# Sheet_2.net
KiCad netlist of a schematic drawn in Altium Designer
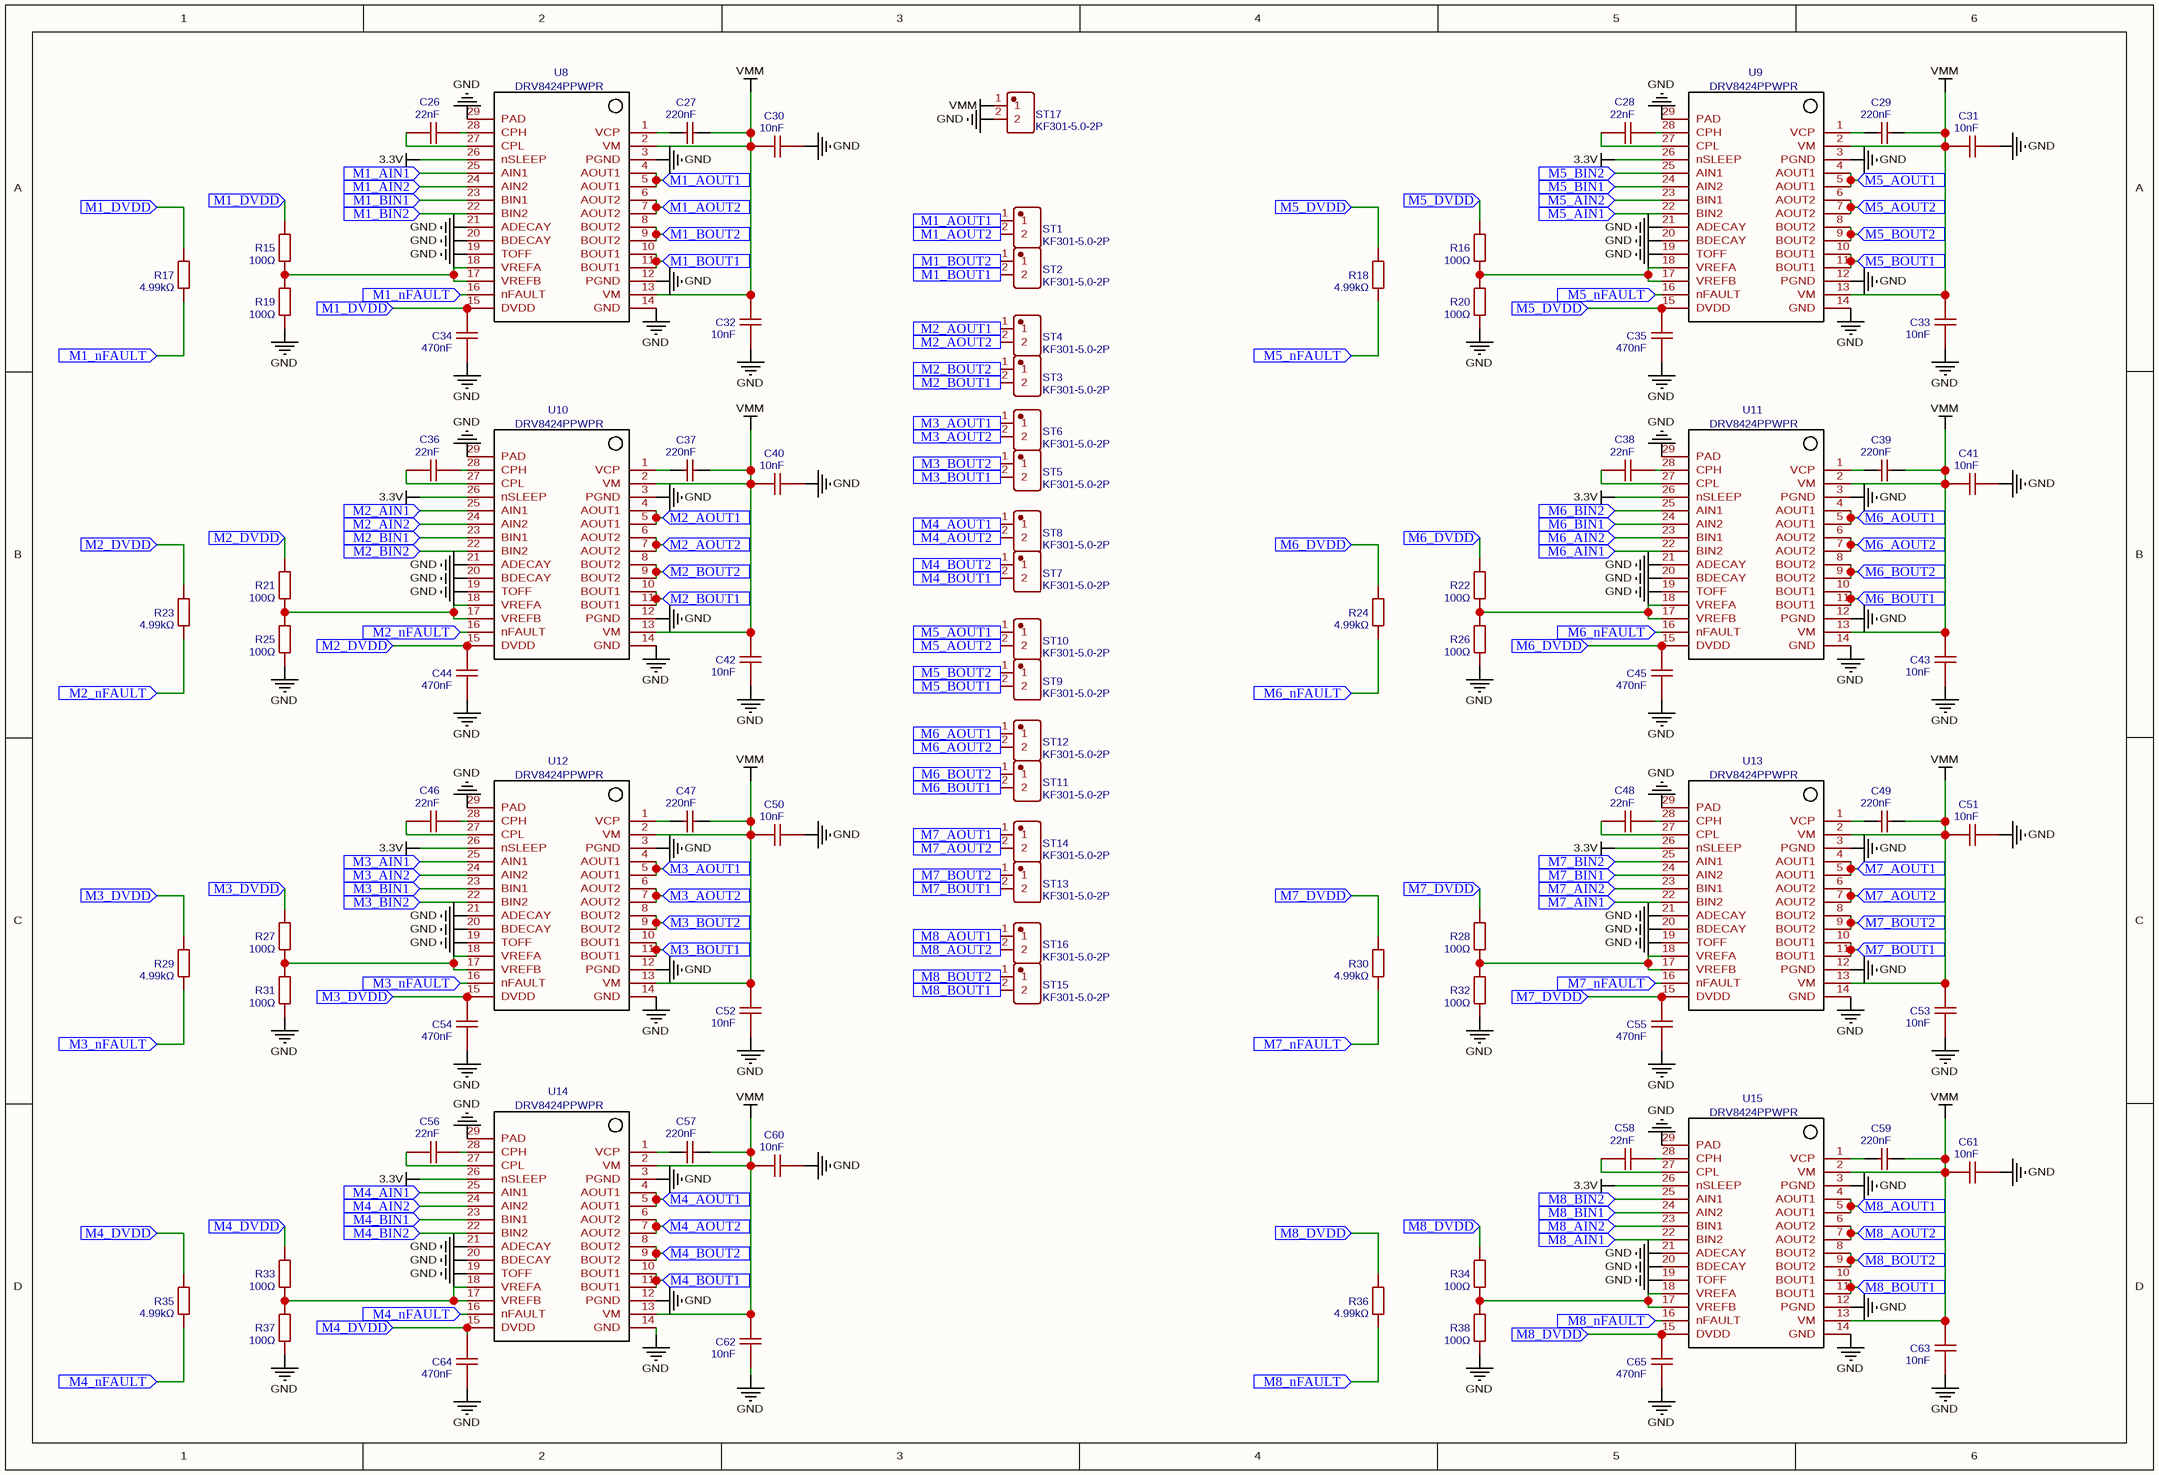
[diagram p0: Sheet_2.schdoc]

(export (version "E")
  (design (tool "Eeschema 10.0.6"))
  (components
    (comp (ref "C26")
      (value "22nF")
      (fields
        (field (name "BOM_SUPPLIER PART") "C561834")
        (field (name "BOM_MANUFACTURER PART") "C0805C223K1RACAUTO")
        (field (name "CONTRIBUTOR") "LCSC")
      )
      (libsource (lib "altium-import") (part "root_0_22nF_"))
    )
    (comp (ref "C27")
      (value "220nF")
      (fields
        (field (name "BOM_MANUFACTURER PART") "CC0805KRX7R8BB224")
        (field (name "BOM_SUPPLIER PART") "C107139")
      )
      (libsource (lib "altium-import") (part "root_0_220nF_"))
    )
    (comp (ref "C28")
      (value "22nF")
      (fields
        (field (name "BOM_SUPPLIER PART") "C561834")
        (field (name "BOM_MANUFACTURER PART") "C0805C223K1RACAUTO")
        (field (name "CONTRIBUTOR") "LCSC")
      )
      (libsource (lib "altium-import") (part "root_0_22nF_"))
    )
    (comp (ref "C29")
      (value "220nF")
      (fields
        (field (name "BOM_MANUFACTURER PART") "CC0805KRX7R8BB224")
        (field (name "BOM_SUPPLIER PART") "C107139")
      )
      (libsource (lib "altium-import") (part "root_0_220nF_"))
    )
    (comp (ref "C30")
      (value "10nF")
      (fields
        (field (name "BOM_MANUFACTURER PART") "CC0805KRX7R9BB103")
        (field (name "BOM_SUPPLIER PART") "C83170")
      )
      (libsource (lib "altium-import") (part "root_2_10nF_"))
    )
    (comp (ref "C31")
      (value "10nF")
      (fields
        (field (name "BOM_MANUFACTURER PART") "CC0805KRX7R9BB103")
        (field (name "BOM_SUPPLIER PART") "C83170")
      )
      (libsource (lib "altium-import") (part "root_2_10nF_"))
    )
    (comp (ref "C32")
      (value "10nF")
      (fields
        (field (name "BOM_MANUFACTURER PART") "CC0805KRX7R9BB103")
        (field (name "BOM_SUPPLIER PART") "C83170")
      )
      (libsource (lib "altium-import") (part "root_3_10nF_"))
    )
    (comp (ref "C33")
      (value "10nF")
      (fields
        (field (name "BOM_MANUFACTURER PART") "CC0805KRX7R9BB103")
        (field (name "BOM_SUPPLIER PART") "C83170")
      )
      (libsource (lib "altium-import") (part "root_3_10nF_"))
    )
    (comp (ref "C34")
      (value "470nF")
      (fields
        (field (name "BOM_SUPPLIER PART") "C520079")
        (field (name "BOM_MANUFACTURER PART") "CC0805JKX7R7BB474")
        (field (name "CONTRIBUTOR") "LCSC")
      )
      (libsource (lib "altium-import") (part "root_3_470nF_"))
    )
    (comp (ref "C35")
      (value "470nF")
      (fields
        (field (name "BOM_SUPPLIER PART") "C520079")
        (field (name "BOM_MANUFACTURER PART") "CC0805JKX7R7BB474")
        (field (name "CONTRIBUTOR") "LCSC")
      )
      (libsource (lib "altium-import") (part "root_3_470nF_"))
    )
    (comp (ref "C36")
      (value "22nF")
      (fields
        (field (name "BOM_SUPPLIER PART") "C561834")
        (field (name "BOM_MANUFACTURER PART") "C0805C223K1RACAUTO")
        (field (name "CONTRIBUTOR") "LCSC")
      )
      (libsource (lib "altium-import") (part "root_0_22nF_"))
    )
    (comp (ref "C37")
      (value "220nF")
      (fields
        (field (name "BOM_MANUFACTURER PART") "CC0805KRX7R8BB224")
        (field (name "BOM_SUPPLIER PART") "C107139")
      )
      (libsource (lib "altium-import") (part "root_0_220nF_"))
    )
    (comp (ref "C38")
      (value "22nF")
      (fields
        (field (name "BOM_SUPPLIER PART") "C561834")
        (field (name "BOM_MANUFACTURER PART") "C0805C223K1RACAUTO")
        (field (name "CONTRIBUTOR") "LCSC")
      )
      (libsource (lib "altium-import") (part "root_0_22nF_"))
    )
    (comp (ref "C39")
      (value "220nF")
      (fields
        (field (name "BOM_MANUFACTURER PART") "CC0805KRX7R8BB224")
        (field (name "BOM_SUPPLIER PART") "C107139")
      )
      (libsource (lib "altium-import") (part "root_0_220nF_"))
    )
    (comp (ref "C40")
      (value "10nF")
      (fields
        (field (name "BOM_MANUFACTURER PART") "CC0805KRX7R9BB103")
        (field (name "BOM_SUPPLIER PART") "C83170")
      )
      (libsource (lib "altium-import") (part "root_2_10nF_"))
    )
    (comp (ref "C41")
      (value "10nF")
      (fields
        (field (name "BOM_MANUFACTURER PART") "CC0805KRX7R9BB103")
        (field (name "BOM_SUPPLIER PART") "C83170")
      )
      (libsource (lib "altium-import") (part "root_2_10nF_"))
    )
    (comp (ref "C42")
      (value "10nF")
      (fields
        (field (name "BOM_MANUFACTURER PART") "CC0805KRX7R9BB103")
        (field (name "BOM_SUPPLIER PART") "C83170")
      )
      (libsource (lib "altium-import") (part "root_3_10nF_"))
    )
    (comp (ref "C43")
      (value "10nF")
      (fields
        (field (name "BOM_MANUFACTURER PART") "CC0805KRX7R9BB103")
        (field (name "BOM_SUPPLIER PART") "C83170")
      )
      (libsource (lib "altium-import") (part "root_3_10nF_"))
    )
    (comp (ref "C44")
      (value "470nF")
      (fields
        (field (name "BOM_SUPPLIER PART") "C520079")
        (field (name "BOM_MANUFACTURER PART") "CC0805JKX7R7BB474")
        (field (name "CONTRIBUTOR") "LCSC")
      )
      (libsource (lib "altium-import") (part "root_3_470nF_"))
    )
    (comp (ref "C45")
      (value "470nF")
      (fields
        (field (name "BOM_SUPPLIER PART") "C520079")
        (field (name "BOM_MANUFACTURER PART") "CC0805JKX7R7BB474")
        (field (name "CONTRIBUTOR") "LCSC")
      )
      (libsource (lib "altium-import") (part "root_3_470nF_"))
    )
    (comp (ref "C46")
      (value "22nF")
      (fields
        (field (name "BOM_SUPPLIER PART") "C561834")
        (field (name "BOM_MANUFACTURER PART") "C0805C223K1RACAUTO")
        (field (name "CONTRIBUTOR") "LCSC")
      )
      (libsource (lib "altium-import") (part "root_0_22nF_"))
    )
    (comp (ref "C47")
      (value "220nF")
      (fields
        (field (name "BOM_MANUFACTURER PART") "CC0805KRX7R8BB224")
        (field (name "BOM_SUPPLIER PART") "C107139")
      )
      (libsource (lib "altium-import") (part "root_0_220nF_"))
    )
    (comp (ref "C48")
      (value "22nF")
      (fields
        (field (name "BOM_SUPPLIER PART") "C561834")
        (field (name "BOM_MANUFACTURER PART") "C0805C223K1RACAUTO")
        (field (name "CONTRIBUTOR") "LCSC")
      )
      (libsource (lib "altium-import") (part "root_0_22nF_"))
    )
    (comp (ref "C49")
      (value "220nF")
      (fields
        (field (name "BOM_MANUFACTURER PART") "CC0805KRX7R8BB224")
        (field (name "BOM_SUPPLIER PART") "C107139")
      )
      (libsource (lib "altium-import") (part "root_0_220nF_"))
    )
    (comp (ref "C50")
      (value "10nF")
      (fields
        (field (name "BOM_MANUFACTURER PART") "CC0805KRX7R9BB103")
        (field (name "BOM_SUPPLIER PART") "C83170")
      )
      (libsource (lib "altium-import") (part "root_2_10nF_"))
    )
    (comp (ref "C51")
      (value "10nF")
      (fields
        (field (name "BOM_MANUFACTURER PART") "CC0805KRX7R9BB103")
        (field (name "BOM_SUPPLIER PART") "C83170")
      )
      (libsource (lib "altium-import") (part "root_2_10nF_"))
    )
    (comp (ref "C52")
      (value "10nF")
      (fields
        (field (name "BOM_MANUFACTURER PART") "CC0805KRX7R9BB103")
        (field (name "BOM_SUPPLIER PART") "C83170")
      )
      (libsource (lib "altium-import") (part "root_3_10nF_"))
    )
    (comp (ref "C53")
      (value "10nF")
      (fields
        (field (name "BOM_MANUFACTURER PART") "CC0805KRX7R9BB103")
        (field (name "BOM_SUPPLIER PART") "C83170")
      )
      (libsource (lib "altium-import") (part "root_3_10nF_"))
    )
    (comp (ref "C54")
      (value "470nF")
      (fields
        (field (name "BOM_SUPPLIER PART") "C520079")
        (field (name "BOM_MANUFACTURER PART") "CC0805JKX7R7BB474")
        (field (name "CONTRIBUTOR") "LCSC")
      )
      (libsource (lib "altium-import") (part "root_3_470nF_"))
    )
    (comp (ref "C55")
      (value "470nF")
      (fields
        (field (name "BOM_SUPPLIER PART") "C520079")
        (field (name "BOM_MANUFACTURER PART") "CC0805JKX7R7BB474")
        (field (name "CONTRIBUTOR") "LCSC")
      )
      (libsource (lib "altium-import") (part "root_3_470nF_"))
    )
    (comp (ref "C56")
      (value "22nF")
      (fields
        (field (name "BOM_SUPPLIER PART") "C561834")
        (field (name "BOM_MANUFACTURER PART") "C0805C223K1RACAUTO")
        (field (name "CONTRIBUTOR") "LCSC")
      )
      (libsource (lib "altium-import") (part "root_0_22nF_"))
    )
    (comp (ref "C57")
      (value "220nF")
      (fields
        (field (name "BOM_MANUFACTURER PART") "CC0805KRX7R8BB224")
        (field (name "BOM_SUPPLIER PART") "C107139")
      )
      (libsource (lib "altium-import") (part "root_0_220nF_"))
    )
    (comp (ref "C58")
      (value "22nF")
      (fields
        (field (name "BOM_SUPPLIER PART") "C561834")
        (field (name "BOM_MANUFACTURER PART") "C0805C223K1RACAUTO")
        (field (name "CONTRIBUTOR") "LCSC")
      )
      (libsource (lib "altium-import") (part "root_0_22nF_"))
    )
    (comp (ref "C59")
      (value "220nF")
      (fields
        (field (name "BOM_MANUFACTURER PART") "CC0805KRX7R8BB224")
        (field (name "BOM_SUPPLIER PART") "C107139")
      )
      (libsource (lib "altium-import") (part "root_0_220nF_"))
    )
    (comp (ref "C60")
      (value "10nF")
      (fields
        (field (name "BOM_MANUFACTURER PART") "CC0805KRX7R9BB103")
        (field (name "BOM_SUPPLIER PART") "C83170")
      )
      (libsource (lib "altium-import") (part "root_2_10nF_"))
    )
    (comp (ref "C61")
      (value "10nF")
      (fields
        (field (name "BOM_MANUFACTURER PART") "CC0805KRX7R9BB103")
        (field (name "BOM_SUPPLIER PART") "C83170")
      )
      (libsource (lib "altium-import") (part "root_2_10nF_"))
    )
    (comp (ref "C62")
      (value "10nF")
      (fields
        (field (name "BOM_MANUFACTURER PART") "CC0805KRX7R9BB103")
        (field (name "BOM_SUPPLIER PART") "C83170")
      )
      (libsource (lib "altium-import") (part "root_3_10nF_"))
    )
    (comp (ref "C63")
      (value "10nF")
      (fields
        (field (name "BOM_MANUFACTURER PART") "CC0805KRX7R9BB103")
        (field (name "BOM_SUPPLIER PART") "C83170")
      )
      (libsource (lib "altium-import") (part "root_3_10nF_"))
    )
    (comp (ref "C64")
      (value "470nF")
      (fields
        (field (name "BOM_SUPPLIER PART") "C520079")
        (field (name "BOM_MANUFACTURER PART") "CC0805JKX7R7BB474")
        (field (name "CONTRIBUTOR") "LCSC")
      )
      (libsource (lib "altium-import") (part "root_3_470nF_"))
    )
    (comp (ref "C65")
      (value "470nF")
      (fields
        (field (name "BOM_SUPPLIER PART") "C520079")
        (field (name "BOM_MANUFACTURER PART") "CC0805JKX7R7BB474")
        (field (name "CONTRIBUTOR") "LCSC")
      )
      (libsource (lib "altium-import") (part "root_3_470nF_"))
    )
    (comp (ref "R15")
      (value "100Ω")
      (fields
        (field (name "BOM_SUPPLIER PART") "C176206")
        (field (name "BOM_MANUFACTURER PART") "QR0805J100RP05")
        (field (name "CONTRIBUTOR") "LCSC")
      )
      (libsource (lib "altium-import") (part "root_1_100Ω_"))
    )
    (comp (ref "R16")
      (value "100Ω")
      (fields
        (field (name "BOM_SUPPLIER PART") "C176206")
        (field (name "BOM_MANUFACTURER PART") "QR0805J100RP05")
        (field (name "CONTRIBUTOR") "LCSC")
      )
      (libsource (lib "altium-import") (part "root_1_100Ω_"))
    )
    (comp (ref "R17")
      (value "4.99kΩ")
      (fields
        (field (name "BOM_SUPPLIER PART") "C325814")
        (field (name "BOM_MANUFACTURER PART") "RMC08054.99K1%N")
        (field (name "CONTRIBUTOR") "LCSC")
      )
      (libsource (lib "altium-import") (part "root_1_4.99kΩ_"))
    )
    (comp (ref "R18")
      (value "4.99kΩ")
      (fields
        (field (name "BOM_SUPPLIER PART") "C325814")
        (field (name "BOM_MANUFACTURER PART") "RMC08054.99K1%N")
        (field (name "CONTRIBUTOR") "LCSC")
      )
      (libsource (lib "altium-import") (part "root_1_4.99kΩ_"))
    )
    (comp (ref "R19")
      (value "100Ω")
      (fields
        (field (name "BOM_SUPPLIER PART") "C176206")
        (field (name "BOM_MANUFACTURER PART") "QR0805J100RP05")
        (field (name "CONTRIBUTOR") "LCSC")
      )
      (libsource (lib "altium-import") (part "root_1_100Ω_"))
    )
    (comp (ref "R20")
      (value "100Ω")
      (fields
        (field (name "BOM_SUPPLIER PART") "C176206")
        (field (name "BOM_MANUFACTURER PART") "QR0805J100RP05")
        (field (name "CONTRIBUTOR") "LCSC")
      )
      (libsource (lib "altium-import") (part "root_1_100Ω_"))
    )
    (comp (ref "R21")
      (value "100Ω")
      (fields
        (field (name "BOM_SUPPLIER PART") "C176206")
        (field (name "BOM_MANUFACTURER PART") "QR0805J100RP05")
        (field (name "CONTRIBUTOR") "LCSC")
      )
      (libsource (lib "altium-import") (part "root_1_100Ω_"))
    )
    (comp (ref "R22")
      (value "100Ω")
      (fields
        (field (name "BOM_SUPPLIER PART") "C176206")
        (field (name "BOM_MANUFACTURER PART") "QR0805J100RP05")
        (field (name "CONTRIBUTOR") "LCSC")
      )
      (libsource (lib "altium-import") (part "root_1_100Ω_"))
    )
    (comp (ref "R23")
      (value "4.99kΩ")
      (fields
        (field (name "BOM_SUPPLIER PART") "C325814")
        (field (name "BOM_MANUFACTURER PART") "RMC08054.99K1%N")
        (field (name "CONTRIBUTOR") "LCSC")
      )
      (libsource (lib "altium-import") (part "root_1_4.99kΩ_"))
    )
    (comp (ref "R24")
      (value "4.99kΩ")
      (fields
        (field (name "BOM_SUPPLIER PART") "C325814")
        (field (name "BOM_MANUFACTURER PART") "RMC08054.99K1%N")
        (field (name "CONTRIBUTOR") "LCSC")
      )
      (libsource (lib "altium-import") (part "root_1_4.99kΩ_"))
    )
    (comp (ref "R25")
      (value "100Ω")
      (fields
        (field (name "BOM_SUPPLIER PART") "C176206")
        (field (name "BOM_MANUFACTURER PART") "QR0805J100RP05")
        (field (name "CONTRIBUTOR") "LCSC")
      )
      (libsource (lib "altium-import") (part "root_1_100Ω_"))
    )
    (comp (ref "R26")
      (value "100Ω")
      (fields
        (field (name "BOM_SUPPLIER PART") "C176206")
        (field (name "BOM_MANUFACTURER PART") "QR0805J100RP05")
        (field (name "CONTRIBUTOR") "LCSC")
      )
      (libsource (lib "altium-import") (part "root_1_100Ω_"))
    )
    (comp (ref "R27")
      (value "100Ω")
      (fields
        (field (name "BOM_SUPPLIER PART") "C176206")
        (field (name "BOM_MANUFACTURER PART") "QR0805J100RP05")
        (field (name "CONTRIBUTOR") "LCSC")
      )
      (libsource (lib "altium-import") (part "root_1_100Ω_"))
    )
    (comp (ref "R28")
      (value "100Ω")
      (fields
        (field (name "BOM_SUPPLIER PART") "C176206")
        (field (name "BOM_MANUFACTURER PART") "QR0805J100RP05")
        (field (name "CONTRIBUTOR") "LCSC")
      )
      (libsource (lib "altium-import") (part "root_1_100Ω_"))
    )
    (comp (ref "R29")
      (value "4.99kΩ")
      (fields
        (field (name "BOM_SUPPLIER PART") "C325814")
        (field (name "BOM_MANUFACTURER PART") "RMC08054.99K1%N")
        (field (name "CONTRIBUTOR") "LCSC")
      )
      (libsource (lib "altium-import") (part "root_1_4.99kΩ_"))
    )
    (comp (ref "R30")
      (value "4.99kΩ")
      (fields
        (field (name "BOM_SUPPLIER PART") "C325814")
        (field (name "BOM_MANUFACTURER PART") "RMC08054.99K1%N")
        (field (name "CONTRIBUTOR") "LCSC")
      )
      (libsource (lib "altium-import") (part "root_1_4.99kΩ_"))
    )
    (comp (ref "R31")
      (value "100Ω")
      (fields
        (field (name "BOM_SUPPLIER PART") "C176206")
        (field (name "BOM_MANUFACTURER PART") "QR0805J100RP05")
        (field (name "CONTRIBUTOR") "LCSC")
      )
      (libsource (lib "altium-import") (part "root_1_100Ω_"))
    )
    (comp (ref "R32")
      (value "100Ω")
      (fields
        (field (name "BOM_SUPPLIER PART") "C176206")
        (field (name "BOM_MANUFACTURER PART") "QR0805J100RP05")
        (field (name "CONTRIBUTOR") "LCSC")
      )
      (libsource (lib "altium-import") (part "root_1_100Ω_"))
    )
    (comp (ref "R33")
      (value "100Ω")
      (fields
        (field (name "BOM_SUPPLIER PART") "C176206")
        (field (name "BOM_MANUFACTURER PART") "QR0805J100RP05")
        (field (name "CONTRIBUTOR") "LCSC")
      )
      (libsource (lib "altium-import") (part "root_1_100Ω_"))
    )
    (comp (ref "R34")
      (value "100Ω")
      (fields
        (field (name "BOM_SUPPLIER PART") "C176206")
        (field (name "BOM_MANUFACTURER PART") "QR0805J100RP05")
        (field (name "CONTRIBUTOR") "LCSC")
      )
      (libsource (lib "altium-import") (part "root_1_100Ω_"))
    )
    (comp (ref "R35")
      (value "4.99kΩ")
      (fields
        (field (name "BOM_SUPPLIER PART") "C325814")
        (field (name "BOM_MANUFACTURER PART") "RMC08054.99K1%N")
        (field (name "CONTRIBUTOR") "LCSC")
      )
      (libsource (lib "altium-import") (part "root_1_4.99kΩ_"))
    )
    (comp (ref "R36")
      (value "4.99kΩ")
      (fields
        (field (name "BOM_SUPPLIER PART") "C325814")
        (field (name "BOM_MANUFACTURER PART") "RMC08054.99K1%N")
        (field (name "CONTRIBUTOR") "LCSC")
      )
      (libsource (lib "altium-import") (part "root_1_4.99kΩ_"))
    )
    (comp (ref "R37")
      (value "100Ω")
      (fields
        (field (name "BOM_SUPPLIER PART") "C176206")
        (field (name "BOM_MANUFACTURER PART") "QR0805J100RP05")
        (field (name "CONTRIBUTOR") "LCSC")
      )
      (libsource (lib "altium-import") (part "root_1_100Ω_"))
    )
    (comp (ref "R38")
      (value "100Ω")
      (fields
        (field (name "BOM_SUPPLIER PART") "C176206")
        (field (name "BOM_MANUFACTURER PART") "QR0805J100RP05")
        (field (name "CONTRIBUTOR") "LCSC")
      )
      (libsource (lib "altium-import") (part "root_1_100Ω_"))
    )
    (comp (ref "ST1")
      (value "KF301-5.0-2P")
      (fields (field (name "BOM_SUPPLIER PART") "C474881") (field (name "CONTRIBUTOR") "LCSC"))
      (libsource (lib "altium-import") (part "root_0_KF301-5.0-2P_"))
    )
    (comp (ref "ST2")
      (value "KF301-5.0-2P")
      (fields (field (name "BOM_SUPPLIER PART") "C474881") (field (name "CONTRIBUTOR") "LCSC"))
      (libsource (lib "altium-import") (part "root_0_KF301-5.0-2P_"))
    )
    (comp (ref "ST3")
      (value "KF301-5.0-2P")
      (fields (field (name "BOM_SUPPLIER PART") "C474881") (field (name "CONTRIBUTOR") "LCSC"))
      (libsource (lib "altium-import") (part "root_0_KF301-5.0-2P_"))
    )
    (comp (ref "ST4")
      (value "KF301-5.0-2P")
      (fields (field (name "BOM_SUPPLIER PART") "C474881") (field (name "CONTRIBUTOR") "LCSC"))
      (libsource (lib "altium-import") (part "root_0_KF301-5.0-2P_"))
    )
    (comp (ref "ST5")
      (value "KF301-5.0-2P")
      (fields (field (name "BOM_SUPPLIER PART") "C474881") (field (name "CONTRIBUTOR") "LCSC"))
      (libsource (lib "altium-import") (part "root_0_KF301-5.0-2P_"))
    )
    (comp (ref "ST6")
      (value "KF301-5.0-2P")
      (fields (field (name "BOM_SUPPLIER PART") "C474881") (field (name "CONTRIBUTOR") "LCSC"))
      (libsource (lib "altium-import") (part "root_0_KF301-5.0-2P_"))
    )
    (comp (ref "ST7")
      (value "KF301-5.0-2P")
      (fields (field (name "BOM_SUPPLIER PART") "C474881") (field (name "CONTRIBUTOR") "LCSC"))
      (libsource (lib "altium-import") (part "root_0_KF301-5.0-2P_"))
    )
    (comp (ref "ST8")
      (value "KF301-5.0-2P")
      (fields (field (name "BOM_SUPPLIER PART") "C474881") (field (name "CONTRIBUTOR") "LCSC"))
      (libsource (lib "altium-import") (part "root_0_KF301-5.0-2P_"))
    )
    (comp (ref "ST9")
      (value "KF301-5.0-2P")
      (fields (field (name "BOM_SUPPLIER PART") "C474881") (field (name "CONTRIBUTOR") "LCSC"))
      (libsource (lib "altium-import") (part "root_0_KF301-5.0-2P_"))
    )
    (comp (ref "ST10")
      (value "KF301-5.0-2P")
      (fields (field (name "BOM_SUPPLIER PART") "C474881") (field (name "CONTRIBUTOR") "LCSC"))
      (libsource (lib "altium-import") (part "root_0_KF301-5.0-2P_"))
    )
    (comp (ref "ST11")
      (value "KF301-5.0-2P")
      (fields (field (name "BOM_SUPPLIER PART") "C474881") (field (name "CONTRIBUTOR") "LCSC"))
      (libsource (lib "altium-import") (part "root_0_KF301-5.0-2P_"))
    )
    (comp (ref "ST12")
      (value "KF301-5.0-2P")
      (fields (field (name "BOM_SUPPLIER PART") "C474881") (field (name "CONTRIBUTOR") "LCSC"))
      (libsource (lib "altium-import") (part "root_0_KF301-5.0-2P_"))
    )
    (comp (ref "ST13")
      (value "KF301-5.0-2P")
      (fields (field (name "BOM_SUPPLIER PART") "C474881") (field (name "CONTRIBUTOR") "LCSC"))
      (libsource (lib "altium-import") (part "root_0_KF301-5.0-2P_"))
    )
    (comp (ref "ST14")
      (value "KF301-5.0-2P")
      (fields (field (name "BOM_SUPPLIER PART") "C474881") (field (name "CONTRIBUTOR") "LCSC"))
      (libsource (lib "altium-import") (part "root_0_KF301-5.0-2P_"))
    )
    (comp (ref "ST15")
      (value "KF301-5.0-2P")
      (fields (field (name "BOM_SUPPLIER PART") "C474881") (field (name "CONTRIBUTOR") "LCSC"))
      (libsource (lib "altium-import") (part "root_0_KF301-5.0-2P_"))
    )
    (comp (ref "ST16")
      (value "KF301-5.0-2P")
      (fields (field (name "BOM_SUPPLIER PART") "C474881") (field (name "CONTRIBUTOR") "LCSC"))
      (libsource (lib "altium-import") (part "root_0_KF301-5.0-2P_"))
    )
    (comp (ref "ST17")
      (value "KF301-5.0-2P")
      (fields (field (name "BOM_SUPPLIER PART") "C474881") (field (name "CONTRIBUTOR") "LCSC"))
      (libsource (lib "altium-import") (part "root_0_KF301-5.0-2P_"))
    )
    (comp (ref "U8")
      (value "DRV8424PPWPR")
      (fields (field (name "CONTRIBUTOR") "吳東燁"))
      (libsource (lib "altium-import") (part "root_0_DRV8424PPWPR_"))
    )
    (comp (ref "U9")
      (value "DRV8424PPWPR")
      (fields (field (name "CONTRIBUTOR") "吳東燁"))
      (libsource (lib "altium-import") (part "root_0_DRV8424PPWPR_"))
    )
    (comp (ref "U10")
      (value "DRV8424PPWPR")
      (fields (field (name "CONTRIBUTOR") "吳東燁"))
      (libsource (lib "altium-import") (part "root_0_DRV8424PPWPR_"))
    )
    (comp (ref "U11")
      (value "DRV8424PPWPR")
      (fields (field (name "CONTRIBUTOR") "吳東燁"))
      (libsource (lib "altium-import") (part "root_0_DRV8424PPWPR_"))
    )
    (comp (ref "U12")
      (value "DRV8424PPWPR")
      (fields (field (name "CONTRIBUTOR") "吳東燁"))
      (libsource (lib "altium-import") (part "root_0_DRV8424PPWPR_"))
    )
    (comp (ref "U13")
      (value "DRV8424PPWPR")
      (fields (field (name "CONTRIBUTOR") "吳東燁"))
      (libsource (lib "altium-import") (part "root_0_DRV8424PPWPR_"))
    )
    (comp (ref "U14")
      (value "DRV8424PPWPR")
      (fields (field (name "CONTRIBUTOR") "吳東燁"))
      (libsource (lib "altium-import") (part "root_0_DRV8424PPWPR_"))
    )
    (comp (ref "U15")
      (value "DRV8424PPWPR")
      (fields (field (name "CONTRIBUTOR") "吳東燁"))
      (libsource (lib "altium-import") (part "root_0_DRV8424PPWPR_"))
    )
  )
  (nets
    (net (code "1") (name "/M1_AIN1") (class "Default")
      (node (ref "U8") (pin "25") (pinfunction "AIN1_25") (pintype "passive"))
    )
    (net (code "2") (name "/M1_AIN2") (class "Default")
      (node (ref "U8") (pin "24") (pinfunction "AIN2_24") (pintype "passive"))
    )
    (net (code "3") (name "/M1_AOUT1") (class "Default")
      (node (ref "ST1") (pin "1") (pinfunction "1_1") (pintype "passive"))
      (node (ref "U8") (pin "4") (pinfunction "AOUT1_4") (pintype "passive"))
      (node (ref "U8") (pin "5") (pinfunction "AOUT1_5") (pintype "passive"))
    )
    (net (code "4") (name "/M1_AOUT2") (class "Default")
      (node (ref "ST1") (pin "2") (pinfunction "2_2") (pintype "passive"))
      (node (ref "U8") (pin "6") (pinfunction "AOUT2_6") (pintype "passive"))
      (node (ref "U8") (pin "7") (pinfunction "AOUT2_7") (pintype "passive"))
    )
    (net (code "5") (name "/M1_BIN1") (class "Default")
      (node (ref "U8") (pin "23") (pinfunction "BIN1_23") (pintype "passive"))
    )
    (net (code "6") (name "/M1_BIN2") (class "Default")
      (node (ref "U8") (pin "22") (pinfunction "BIN2_22") (pintype "passive"))
    )
    (net (code "7") (name "/M1_BOUT1") (class "Default")
      (node (ref "ST2") (pin "2") (pinfunction "2_2") (pintype "passive"))
      (node (ref "U8") (pin "10") (pinfunction "BOUT1_10") (pintype "passive"))
      (node (ref "U8") (pin "11") (pinfunction "BOUT1_11") (pintype "passive"))
    )
    (net (code "8") (name "/M1_BOUT2") (class "Default")
      (node (ref "ST2") (pin "1") (pinfunction "1_1") (pintype "passive"))
      (node (ref "U8") (pin "8") (pinfunction "BOUT2_8") (pintype "passive"))
      (node (ref "U8") (pin "9") (pinfunction "BOUT2_9") (pintype "passive"))
    )
    (net (code "9") (name "/M1_DVDD") (class "Default")
      (node (ref "C34") (pin "1") (pinfunction "1_1") (pintype "passive"))
      (node (ref "R15") (pin "2") (pinfunction "2_2") (pintype "passive"))
      (node (ref "R17") (pin "2") (pinfunction "2_2") (pintype "passive"))
      (node (ref "U8") (pin "15") (pinfunction "DVDD_15") (pintype "passive"))
    )
    (net (code "10") (name "/M1_nFAULT") (class "Default")
      (node (ref "R17") (pin "1") (pinfunction "1_1") (pintype "passive"))
      (node (ref "U8") (pin "16") (pinfunction "nFAULT_16") (pintype "passive"))
    )
    (net (code "11") (name "/M2_AIN1") (class "Default")
      (node (ref "U10") (pin "25") (pinfunction "AIN1_25") (pintype "passive"))
    )
    (net (code "12") (name "/M2_AIN2") (class "Default")
      (node (ref "U10") (pin "24") (pinfunction "AIN2_24") (pintype "passive"))
    )
    (net (code "13") (name "/M2_AOUT1") (class "Default")
      (node (ref "ST4") (pin "1") (pinfunction "1_1") (pintype "passive"))
      (node (ref "U10") (pin "4") (pinfunction "AOUT1_4") (pintype "passive"))
      (node (ref "U10") (pin "5") (pinfunction "AOUT1_5") (pintype "passive"))
    )
    (net (code "14") (name "/M2_AOUT2") (class "Default")
      (node (ref "ST4") (pin "2") (pinfunction "2_2") (pintype "passive"))
      (node (ref "U10") (pin "6") (pinfunction "AOUT2_6") (pintype "passive"))
      (node (ref "U10") (pin "7") (pinfunction "AOUT2_7") (pintype "passive"))
    )
    (net (code "15") (name "/M2_BIN1") (class "Default")
      (node (ref "U10") (pin "23") (pinfunction "BIN1_23") (pintype "passive"))
    )
    (net (code "16") (name "/M2_BIN2") (class "Default")
      (node (ref "U10") (pin "22") (pinfunction "BIN2_22") (pintype "passive"))
    )
    (net (code "17") (name "/M2_BOUT1") (class "Default")
      (node (ref "ST3") (pin "2") (pinfunction "2_2") (pintype "passive"))
      (node (ref "U10") (pin "10") (pinfunction "BOUT1_10") (pintype "passive"))
      (node (ref "U10") (pin "11") (pinfunction "BOUT1_11") (pintype "passive"))
    )
    (net (code "18") (name "/M2_BOUT2") (class "Default")
      (node (ref "ST3") (pin "1") (pinfunction "1_1") (pintype "passive"))
      (node (ref "U10") (pin "8") (pinfunction "BOUT2_8") (pintype "passive"))
      (node (ref "U10") (pin "9") (pinfunction "BOUT2_9") (pintype "passive"))
    )
    (net (code "19") (name "/M2_DVDD") (class "Default")
      (node (ref "C44") (pin "1") (pinfunction "1_1") (pintype "passive"))
      (node (ref "R21") (pin "2") (pinfunction "2_2") (pintype "passive"))
      (node (ref "R23") (pin "2") (pinfunction "2_2") (pintype "passive"))
      (node (ref "U10") (pin "15") (pinfunction "DVDD_15") (pintype "passive"))
    )
    (net (code "20") (name "/M2_nFAULT") (class "Default")
      (node (ref "R23") (pin "1") (pinfunction "1_1") (pintype "passive"))
      (node (ref "U10") (pin "16") (pinfunction "nFAULT_16") (pintype "passive"))
    )
    (net (code "21") (name "/M3_AIN1") (class "Default")
      (node (ref "U12") (pin "25") (pinfunction "AIN1_25") (pintype "passive"))
    )
    (net (code "22") (name "/M3_AIN2") (class "Default")
      (node (ref "U12") (pin "24") (pinfunction "AIN2_24") (pintype "passive"))
    )
    (net (code "23") (name "/M3_AOUT1") (class "Default")
      (node (ref "ST6") (pin "1") (pinfunction "1_1") (pintype "passive"))
      (node (ref "U12") (pin "4") (pinfunction "AOUT1_4") (pintype "passive"))
      (node (ref "U12") (pin "5") (pinfunction "AOUT1_5") (pintype "passive"))
    )
    (net (code "24") (name "/M3_AOUT2") (class "Default")
      (node (ref "ST6") (pin "2") (pinfunction "2_2") (pintype "passive"))
      (node (ref "U12") (pin "6") (pinfunction "AOUT2_6") (pintype "passive"))
      (node (ref "U12") (pin "7") (pinfunction "AOUT2_7") (pintype "passive"))
    )
    (net (code "25") (name "/M3_BIN1") (class "Default")
      (node (ref "U12") (pin "23") (pinfunction "BIN1_23") (pintype "passive"))
    )
    (net (code "26") (name "/M3_BIN2") (class "Default")
      (node (ref "U12") (pin "22") (pinfunction "BIN2_22") (pintype "passive"))
    )
    (net (code "27") (name "/M3_BOUT1") (class "Default")
      (node (ref "ST5") (pin "2") (pinfunction "2_2") (pintype "passive"))
      (node (ref "U12") (pin "10") (pinfunction "BOUT1_10") (pintype "passive"))
      (node (ref "U12") (pin "11") (pinfunction "BOUT1_11") (pintype "passive"))
    )
    (net (code "28") (name "/M3_BOUT2") (class "Default")
      (node (ref "ST5") (pin "1") (pinfunction "1_1") (pintype "passive"))
      (node (ref "U12") (pin "8") (pinfunction "BOUT2_8") (pintype "passive"))
      (node (ref "U12") (pin "9") (pinfunction "BOUT2_9") (pintype "passive"))
    )
    (net (code "29") (name "/M3_DVDD") (class "Default")
      (node (ref "C54") (pin "1") (pinfunction "1_1") (pintype "passive"))
      (node (ref "R27") (pin "2") (pinfunction "2_2") (pintype "passive"))
      (node (ref "R29") (pin "2") (pinfunction "2_2") (pintype "passive"))
      (node (ref "U12") (pin "15") (pinfunction "DVDD_15") (pintype "passive"))
    )
    (net (code "30") (name "/M3_nFAULT") (class "Default")
      (node (ref "R29") (pin "1") (pinfunction "1_1") (pintype "passive"))
      (node (ref "U12") (pin "16") (pinfunction "nFAULT_16") (pintype "passive"))
    )
    (net (code "31") (name "/M4_AIN1") (class "Default")
      (node (ref "U14") (pin "25") (pinfunction "AIN1_25") (pintype "passive"))
    )
    (net (code "32") (name "/M4_AIN2") (class "Default")
      (node (ref "U14") (pin "24") (pinfunction "AIN2_24") (pintype "passive"))
    )
    (net (code "33") (name "/M4_AOUT1") (class "Default")
      (node (ref "ST8") (pin "1") (pinfunction "1_1") (pintype "passive"))
      (node (ref "U14") (pin "4") (pinfunction "AOUT1_4") (pintype "passive"))
      (node (ref "U14") (pin "5") (pinfunction "AOUT1_5") (pintype "passive"))
    )
    (net (code "34") (name "/M4_AOUT2") (class "Default")
      (node (ref "ST8") (pin "2") (pinfunction "2_2") (pintype "passive"))
      (node (ref "U14") (pin "6") (pinfunction "AOUT2_6") (pintype "passive"))
      (node (ref "U14") (pin "7") (pinfunction "AOUT2_7") (pintype "passive"))
    )
    (net (code "35") (name "/M4_BIN1") (class "Default")
      (node (ref "U14") (pin "23") (pinfunction "BIN1_23") (pintype "passive"))
    )
    (net (code "36") (name "/M4_BIN2") (class "Default")
      (node (ref "U14") (pin "22") (pinfunction "BIN2_22") (pintype "passive"))
    )
    (net (code "37") (name "/M4_BOUT1") (class "Default")
      (node (ref "ST7") (pin "2") (pinfunction "2_2") (pintype "passive"))
      (node (ref "U14") (pin "10") (pinfunction "BOUT1_10") (pintype "passive"))
      (node (ref "U14") (pin "11") (pinfunction "BOUT1_11") (pintype "passive"))
    )
    (net (code "38") (name "/M4_BOUT2") (class "Default")
      (node (ref "ST7") (pin "1") (pinfunction "1_1") (pintype "passive"))
      (node (ref "U14") (pin "8") (pinfunction "BOUT2_8") (pintype "passive"))
      (node (ref "U14") (pin "9") (pinfunction "BOUT2_9") (pintype "passive"))
    )
    (net (code "39") (name "/M4_DVDD") (class "Default")
      (node (ref "C64") (pin "1") (pinfunction "1_1") (pintype "passive"))
      (node (ref "R33") (pin "2") (pinfunction "2_2") (pintype "passive"))
      (node (ref "R35") (pin "2") (pinfunction "2_2") (pintype "passive"))
      (node (ref "U14") (pin "15") (pinfunction "DVDD_15") (pintype "passive"))
    )
    (net (code "40") (name "/M4_nFAULT") (class "Default")
      (node (ref "R35") (pin "1") (pinfunction "1_1") (pintype "passive"))
      (node (ref "U14") (pin "16") (pinfunction "nFAULT_16") (pintype "passive"))
    )
    (net (code "41") (name "/M5_AIN1") (class "Default")
      (node (ref "U9") (pin "22") (pinfunction "BIN2_22") (pintype "passive"))
    )
    (net (code "42") (name "/M5_AIN2") (class "Default")
      (node (ref "U9") (pin "23") (pinfunction "BIN1_23") (pintype "passive"))
    )
    (net (code "43") (name "/M5_AOUT1") (class "Default")
      (node (ref "ST10") (pin "1") (pinfunction "1_1") (pintype "passive"))
      (node (ref "U9") (pin "4") (pinfunction "AOUT1_4") (pintype "passive"))
      (node (ref "U9") (pin "5") (pinfunction "AOUT1_5") (pintype "passive"))
    )
    (net (code "44") (name "/M5_AOUT2") (class "Default")
      (node (ref "ST10") (pin "2") (pinfunction "2_2") (pintype "passive"))
      (node (ref "U9") (pin "6") (pinfunction "AOUT2_6") (pintype "passive"))
      (node (ref "U9") (pin "7") (pinfunction "AOUT2_7") (pintype "passive"))
    )
    (net (code "45") (name "/M5_BIN1") (class "Default")
      (node (ref "U9") (pin "24") (pinfunction "AIN2_24") (pintype "passive"))
    )
    (net (code "46") (name "/M5_BIN2") (class "Default")
      (node (ref "U9") (pin "25") (pinfunction "AIN1_25") (pintype "passive"))
    )
    (net (code "47") (name "/M5_BOUT1") (class "Default")
      (node (ref "ST9") (pin "2") (pinfunction "2_2") (pintype "passive"))
      (node (ref "U9") (pin "10") (pinfunction "BOUT1_10") (pintype "passive"))
      (node (ref "U9") (pin "11") (pinfunction "BOUT1_11") (pintype "passive"))
    )
    (net (code "48") (name "/M5_BOUT2") (class "Default")
      (node (ref "ST9") (pin "1") (pinfunction "1_1") (pintype "passive"))
      (node (ref "U9") (pin "8") (pinfunction "BOUT2_8") (pintype "passive"))
      (node (ref "U9") (pin "9") (pinfunction "BOUT2_9") (pintype "passive"))
    )
    (net (code "49") (name "/M5_DVDD") (class "Default")
      (node (ref "C35") (pin "1") (pinfunction "1_1") (pintype "passive"))
      (node (ref "R16") (pin "2") (pinfunction "2_2") (pintype "passive"))
      (node (ref "R18") (pin "2") (pinfunction "2_2") (pintype "passive"))
      (node (ref "U9") (pin "15") (pinfunction "DVDD_15") (pintype "passive"))
    )
    (net (code "50") (name "/M5_nFAULT") (class "Default")
      (node (ref "R18") (pin "1") (pinfunction "1_1") (pintype "passive"))
      (node (ref "U9") (pin "16") (pinfunction "nFAULT_16") (pintype "passive"))
    )
    (net (code "51") (name "/M6_AIN1") (class "Default")
      (node (ref "U11") (pin "22") (pinfunction "BIN2_22") (pintype "passive"))
    )
    (net (code "52") (name "/M6_AIN2") (class "Default")
      (node (ref "U11") (pin "23") (pinfunction "BIN1_23") (pintype "passive"))
    )
    (net (code "53") (name "/M6_AOUT1") (class "Default")
      (node (ref "ST12") (pin "1") (pinfunction "1_1") (pintype "passive"))
      (node (ref "U11") (pin "4") (pinfunction "AOUT1_4") (pintype "passive"))
      (node (ref "U11") (pin "5") (pinfunction "AOUT1_5") (pintype "passive"))
    )
    (net (code "54") (name "/M6_AOUT2") (class "Default")
      (node (ref "ST12") (pin "2") (pinfunction "2_2") (pintype "passive"))
      (node (ref "U11") (pin "6") (pinfunction "AOUT2_6") (pintype "passive"))
      (node (ref "U11") (pin "7") (pinfunction "AOUT2_7") (pintype "passive"))
    )
    (net (code "55") (name "/M6_BIN1") (class "Default")
      (node (ref "U11") (pin "24") (pinfunction "AIN2_24") (pintype "passive"))
    )
    (net (code "56") (name "/M6_BIN2") (class "Default")
      (node (ref "U11") (pin "25") (pinfunction "AIN1_25") (pintype "passive"))
    )
    (net (code "57") (name "/M6_BOUT1") (class "Default")
      (node (ref "ST11") (pin "2") (pinfunction "2_2") (pintype "passive"))
      (node (ref "U11") (pin "10") (pinfunction "BOUT1_10") (pintype "passive"))
      (node (ref "U11") (pin "11") (pinfunction "BOUT1_11") (pintype "passive"))
    )
    (net (code "58") (name "/M6_BOUT2") (class "Default")
      (node (ref "ST11") (pin "1") (pinfunction "1_1") (pintype "passive"))
      (node (ref "U11") (pin "8") (pinfunction "BOUT2_8") (pintype "passive"))
      (node (ref "U11") (pin "9") (pinfunction "BOUT2_9") (pintype "passive"))
    )
    (net (code "59") (name "/M6_DVDD") (class "Default")
      (node (ref "C45") (pin "1") (pinfunction "1_1") (pintype "passive"))
      (node (ref "R22") (pin "2") (pinfunction "2_2") (pintype "passive"))
      (node (ref "R24") (pin "2") (pinfunction "2_2") (pintype "passive"))
      (node (ref "U11") (pin "15") (pinfunction "DVDD_15") (pintype "passive"))
    )
    (net (code "60") (name "/M6_nFAULT") (class "Default")
      (node (ref "R24") (pin "1") (pinfunction "1_1") (pintype "passive"))
      (node (ref "U11") (pin "16") (pinfunction "nFAULT_16") (pintype "passive"))
    )
    (net (code "61") (name "/M7_AIN1") (class "Default")
      (node (ref "U13") (pin "22") (pinfunction "BIN2_22") (pintype "passive"))
    )
    (net (code "62") (name "/M7_AIN2") (class "Default")
      (node (ref "U13") (pin "23") (pinfunction "BIN1_23") (pintype "passive"))
    )
    (net (code "63") (name "/M7_AOUT1") (class "Default")
      (node (ref "ST14") (pin "1") (pinfunction "1_1") (pintype "passive"))
      (node (ref "U13") (pin "4") (pinfunction "AOUT1_4") (pintype "passive"))
      (node (ref "U13") (pin "5") (pinfunction "AOUT1_5") (pintype "passive"))
    )
    (net (code "64") (name "/M7_AOUT2") (class "Default")
      (node (ref "ST14") (pin "2") (pinfunction "2_2") (pintype "passive"))
      (node (ref "U13") (pin "6") (pinfunction "AOUT2_6") (pintype "passive"))
      (node (ref "U13") (pin "7") (pinfunction "AOUT2_7") (pintype "passive"))
    )
    (net (code "65") (name "/M7_BIN1") (class "Default")
      (node (ref "U13") (pin "24") (pinfunction "AIN2_24") (pintype "passive"))
    )
    (net (code "66") (name "/M7_BIN2") (class "Default")
      (node (ref "U13") (pin "25") (pinfunction "AIN1_25") (pintype "passive"))
    )
    (net (code "67") (name "/M7_BOUT1") (class "Default")
      (node (ref "ST13") (pin "2") (pinfunction "2_2") (pintype "passive"))
      (node (ref "U13") (pin "10") (pinfunction "BOUT1_10") (pintype "passive"))
      (node (ref "U13") (pin "11") (pinfunction "BOUT1_11") (pintype "passive"))
    )
    (net (code "68") (name "/M7_BOUT2") (class "Default")
      (node (ref "ST13") (pin "1") (pinfunction "1_1") (pintype "passive"))
      (node (ref "U13") (pin "8") (pinfunction "BOUT2_8") (pintype "passive"))
      (node (ref "U13") (pin "9") (pinfunction "BOUT2_9") (pintype "passive"))
    )
    (net (code "69") (name "/M7_DVDD") (class "Default")
      (node (ref "C55") (pin "1") (pinfunction "1_1") (pintype "passive"))
      (node (ref "R28") (pin "2") (pinfunction "2_2") (pintype "passive"))
      (node (ref "R30") (pin "2") (pinfunction "2_2") (pintype "passive"))
      (node (ref "U13") (pin "15") (pinfunction "DVDD_15") (pintype "passive"))
    )
    (net (code "70") (name "/M7_nFAULT") (class "Default")
      (node (ref "R30") (pin "1") (pinfunction "1_1") (pintype "passive"))
      (node (ref "U13") (pin "16") (pinfunction "nFAULT_16") (pintype "passive"))
    )
    (net (code "71") (name "/M8_AIN1") (class "Default")
      (node (ref "U15") (pin "22") (pinfunction "BIN2_22") (pintype "passive"))
    )
    (net (code "72") (name "/M8_AIN2") (class "Default")
      (node (ref "U15") (pin "23") (pinfunction "BIN1_23") (pintype "passive"))
    )
    (net (code "73") (name "/M8_AOUT1") (class "Default")
      (node (ref "ST16") (pin "1") (pinfunction "1_1") (pintype "passive"))
      (node (ref "U15") (pin "4") (pinfunction "AOUT1_4") (pintype "passive"))
      (node (ref "U15") (pin "5") (pinfunction "AOUT1_5") (pintype "passive"))
    )
    (net (code "74") (name "/M8_AOUT2") (class "Default")
      (node (ref "ST16") (pin "2") (pinfunction "2_2") (pintype "passive"))
      (node (ref "U15") (pin "6") (pinfunction "AOUT2_6") (pintype "passive"))
      (node (ref "U15") (pin "7") (pinfunction "AOUT2_7") (pintype "passive"))
    )
    (net (code "75") (name "/M8_BIN1") (class "Default")
      (node (ref "U15") (pin "24") (pinfunction "AIN2_24") (pintype "passive"))
    )
    (net (code "76") (name "/M8_BIN2") (class "Default")
      (node (ref "U15") (pin "25") (pinfunction "AIN1_25") (pintype "passive"))
    )
    (net (code "77") (name "/M8_BOUT1") (class "Default")
      (node (ref "ST15") (pin "2") (pinfunction "2_2") (pintype "passive"))
      (node (ref "U15") (pin "10") (pinfunction "BOUT1_10") (pintype "passive"))
      (node (ref "U15") (pin "11") (pinfunction "BOUT1_11") (pintype "passive"))
    )
    (net (code "78") (name "/M8_BOUT2") (class "Default")
      (node (ref "ST15") (pin "1") (pinfunction "1_1") (pintype "passive"))
      (node (ref "U15") (pin "8") (pinfunction "BOUT2_8") (pintype "passive"))
      (node (ref "U15") (pin "9") (pinfunction "BOUT2_9") (pintype "passive"))
    )
    (net (code "79") (name "/M8_DVDD") (class "Default")
      (node (ref "C65") (pin "1") (pinfunction "1_1") (pintype "passive"))
      (node (ref "R34") (pin "2") (pinfunction "2_2") (pintype "passive"))
      (node (ref "R36") (pin "2") (pinfunction "2_2") (pintype "passive"))
      (node (ref "U15") (pin "15") (pinfunction "DVDD_15") (pintype "passive"))
    )
    (net (code "80") (name "/M8_nFAULT") (class "Default")
      (node (ref "R36") (pin "1") (pinfunction "1_1") (pintype "passive"))
      (node (ref "U15") (pin "16") (pinfunction "nFAULT_16") (pintype "passive"))
    )
    (net (code "81") (name "3.3V") (class "Default")
      (node (ref "U10") (pin "26") (pinfunction "nSLEEP_26") (pintype "passive"))
      (node (ref "U11") (pin "26") (pinfunction "nSLEEP_26") (pintype "passive"))
      (node (ref "U12") (pin "26") (pinfunction "nSLEEP_26") (pintype "passive"))
      (node (ref "U13") (pin "26") (pinfunction "nSLEEP_26") (pintype "passive"))
      (node (ref "U14") (pin "26") (pinfunction "nSLEEP_26") (pintype "passive"))
      (node (ref "U15") (pin "26") (pinfunction "nSLEEP_26") (pintype "passive"))
      (node (ref "U8") (pin "26") (pinfunction "nSLEEP_26") (pintype "passive"))
      (node (ref "U9") (pin "26") (pinfunction "nSLEEP_26") (pintype "passive"))
    )
    (net (code "82") (name "GND") (class "Default")
      (node (ref "C30") (pin "2") (pinfunction "2_2") (pintype "passive"))
      (node (ref "C31") (pin "2") (pinfunction "2_2") (pintype "passive"))
      (node (ref "C32") (pin "2") (pinfunction "2_2") (pintype "passive"))
      (node (ref "C33") (pin "2") (pinfunction "2_2") (pintype "passive"))
      (node (ref "C34") (pin "2") (pinfunction "2_2") (pintype "passive"))
      (node (ref "C35") (pin "2") (pinfunction "2_2") (pintype "passive"))
      (node (ref "C40") (pin "2") (pinfunction "2_2") (pintype "passive"))
      (node (ref "C41") (pin "2") (pinfunction "2_2") (pintype "passive"))
      (node (ref "C42") (pin "2") (pinfunction "2_2") (pintype "passive"))
      (node (ref "C43") (pin "2") (pinfunction "2_2") (pintype "passive"))
      (node (ref "C44") (pin "2") (pinfunction "2_2") (pintype "passive"))
      (node (ref "C45") (pin "2") (pinfunction "2_2") (pintype "passive"))
      (node (ref "C50") (pin "2") (pinfunction "2_2") (pintype "passive"))
      (node (ref "C51") (pin "2") (pinfunction "2_2") (pintype "passive"))
      (node (ref "C52") (pin "2") (pinfunction "2_2") (pintype "passive"))
      (node (ref "C53") (pin "2") (pinfunction "2_2") (pintype "passive"))
      (node (ref "C54") (pin "2") (pinfunction "2_2") (pintype "passive"))
      (node (ref "C55") (pin "2") (pinfunction "2_2") (pintype "passive"))
      (node (ref "C60") (pin "2") (pinfunction "2_2") (pintype "passive"))
      (node (ref "C61") (pin "2") (pinfunction "2_2") (pintype "passive"))
      (node (ref "C62") (pin "2") (pinfunction "2_2") (pintype "passive"))
      (node (ref "C63") (pin "2") (pinfunction "2_2") (pintype "passive"))
      (node (ref "C64") (pin "2") (pinfunction "2_2") (pintype "passive"))
      (node (ref "C65") (pin "2") (pinfunction "2_2") (pintype "passive"))
      (node (ref "R19") (pin "1") (pinfunction "1_1") (pintype "passive"))
      (node (ref "R20") (pin "1") (pinfunction "1_1") (pintype "passive"))
      (node (ref "R25") (pin "1") (pinfunction "1_1") (pintype "passive"))
      (node (ref "R26") (pin "1") (pinfunction "1_1") (pintype "passive"))
      (node (ref "R31") (pin "1") (pinfunction "1_1") (pintype "passive"))
      (node (ref "R32") (pin "1") (pinfunction "1_1") (pintype "passive"))
      (node (ref "R37") (pin "1") (pinfunction "1_1") (pintype "passive"))
      (node (ref "R38") (pin "1") (pinfunction "1_1") (pintype "passive"))
      (node (ref "ST17") (pin "2") (pinfunction "2_2") (pintype "passive"))
      (node (ref "U10") (pin "12") (pinfunction "PGND_12") (pintype "passive"))
      (node (ref "U10") (pin "14") (pinfunction "GND_14") (pintype "passive"))
      (node (ref "U10") (pin "19") (pinfunction "TOFF_19") (pintype "passive"))
      (node (ref "U10") (pin "20") (pinfunction "BDECAY_20") (pintype "passive"))
      (node (ref "U10") (pin "21") (pinfunction "ADECAY_21") (pintype "passive"))
      (node (ref "U10") (pin "29") (pinfunction "PAD_29") (pintype "passive"))
      (node (ref "U10") (pin "3") (pinfunction "PGND_3") (pintype "passive"))
      (node (ref "U11") (pin "12") (pinfunction "PGND_12") (pintype "passive"))
      (node (ref "U11") (pin "14") (pinfunction "GND_14") (pintype "passive"))
      (node (ref "U11") (pin "19") (pinfunction "TOFF_19") (pintype "passive"))
      (node (ref "U11") (pin "20") (pinfunction "BDECAY_20") (pintype "passive"))
      (node (ref "U11") (pin "21") (pinfunction "ADECAY_21") (pintype "passive"))
      (node (ref "U11") (pin "29") (pinfunction "PAD_29") (pintype "passive"))
      (node (ref "U11") (pin "3") (pinfunction "PGND_3") (pintype "passive"))
      (node (ref "U12") (pin "12") (pinfunction "PGND_12") (pintype "passive"))
      (node (ref "U12") (pin "14") (pinfunction "GND_14") (pintype "passive"))
      (node (ref "U12") (pin "19") (pinfunction "TOFF_19") (pintype "passive"))
      (node (ref "U12") (pin "20") (pinfunction "BDECAY_20") (pintype "passive"))
      (node (ref "U12") (pin "21") (pinfunction "ADECAY_21") (pintype "passive"))
      (node (ref "U12") (pin "29") (pinfunction "PAD_29") (pintype "passive"))
      (node (ref "U12") (pin "3") (pinfunction "PGND_3") (pintype "passive"))
      (node (ref "U13") (pin "12") (pinfunction "PGND_12") (pintype "passive"))
      (node (ref "U13") (pin "14") (pinfunction "GND_14") (pintype "passive"))
      (node (ref "U13") (pin "19") (pinfunction "TOFF_19") (pintype "passive"))
      (node (ref "U13") (pin "20") (pinfunction "BDECAY_20") (pintype "passive"))
      (node (ref "U13") (pin "21") (pinfunction "ADECAY_21") (pintype "passive"))
      (node (ref "U13") (pin "29") (pinfunction "PAD_29") (pintype "passive"))
      (node (ref "U13") (pin "3") (pinfunction "PGND_3") (pintype "passive"))
      (node (ref "U14") (pin "12") (pinfunction "PGND_12") (pintype "passive"))
      (node (ref "U14") (pin "14") (pinfunction "GND_14") (pintype "passive"))
      (node (ref "U14") (pin "19") (pinfunction "TOFF_19") (pintype "passive"))
      (node (ref "U14") (pin "20") (pinfunction "BDECAY_20") (pintype "passive"))
      (node (ref "U14") (pin "21") (pinfunction "ADECAY_21") (pintype "passive"))
      (node (ref "U14") (pin "29") (pinfunction "PAD_29") (pintype "passive"))
      (node (ref "U14") (pin "3") (pinfunction "PGND_3") (pintype "passive"))
      (node (ref "U15") (pin "12") (pinfunction "PGND_12") (pintype "passive"))
      (node (ref "U15") (pin "14") (pinfunction "GND_14") (pintype "passive"))
      (node (ref "U15") (pin "19") (pinfunction "TOFF_19") (pintype "passive"))
      (node (ref "U15") (pin "20") (pinfunction "BDECAY_20") (pintype "passive"))
      (node (ref "U15") (pin "21") (pinfunction "ADECAY_21") (pintype "passive"))
      (node (ref "U15") (pin "29") (pinfunction "PAD_29") (pintype "passive"))
      (node (ref "U15") (pin "3") (pinfunction "PGND_3") (pintype "passive"))
      (node (ref "U8") (pin "12") (pinfunction "PGND_12") (pintype "passive"))
      (node (ref "U8") (pin "14") (pinfunction "GND_14") (pintype "passive"))
      (node (ref "U8") (pin "19") (pinfunction "TOFF_19") (pintype "passive"))
      (node (ref "U8") (pin "20") (pinfunction "BDECAY_20") (pintype "passive"))
      (node (ref "U8") (pin "21") (pinfunction "ADECAY_21") (pintype "passive"))
      (node (ref "U8") (pin "29") (pinfunction "PAD_29") (pintype "passive"))
      (node (ref "U8") (pin "3") (pinfunction "PGND_3") (pintype "passive"))
      (node (ref "U9") (pin "12") (pinfunction "PGND_12") (pintype "passive"))
      (node (ref "U9") (pin "14") (pinfunction "GND_14") (pintype "passive"))
      (node (ref "U9") (pin "19") (pinfunction "TOFF_19") (pintype "passive"))
      (node (ref "U9") (pin "20") (pinfunction "BDECAY_20") (pintype "passive"))
      (node (ref "U9") (pin "21") (pinfunction "ADECAY_21") (pintype "passive"))
      (node (ref "U9") (pin "29") (pinfunction "PAD_29") (pintype "passive"))
      (node (ref "U9") (pin "3") (pinfunction "PGND_3") (pintype "passive"))
    )
    (net (code "83") (name "Net-(U8-CPH)") (class "Default")
      (node (ref "C26") (pin "1") (pinfunction "1_1") (pintype "passive"))
      (node (ref "U8") (pin "28") (pinfunction "CPH_28") (pintype "passive"))
    )
    (net (code "84") (name "Net-(U8-CPL)") (class "Default")
      (node (ref "C26") (pin "2") (pinfunction "2_2") (pintype "passive"))
      (node (ref "U8") (pin "27") (pinfunction "CPL_27") (pintype "passive"))
    )
    (net (code "85") (name "Net-(U8-VCP)") (class "Default")
      (node (ref "C27") (pin "2") (pinfunction "2_2") (pintype "passive"))
      (node (ref "U8") (pin "1") (pinfunction "VCP_1") (pintype "passive"))
    )
    (net (code "86") (name "Net-(U8-VREFA)") (class "Default")
      (node (ref "R15") (pin "1") (pinfunction "1_1") (pintype "passive"))
      (node (ref "R19") (pin "2") (pinfunction "2_2") (pintype "passive"))
      (node (ref "U8") (pin "17") (pinfunction "VREFB_17") (pintype "passive"))
      (node (ref "U8") (pin "18") (pinfunction "VREFA_18") (pintype "passive"))
    )
    (net (code "87") (name "Net-(U9-CPH)") (class "Default")
      (node (ref "C28") (pin "1") (pinfunction "1_1") (pintype "passive"))
      (node (ref "U9") (pin "28") (pinfunction "CPH_28") (pintype "passive"))
    )
    (net (code "88") (name "Net-(U9-CPL)") (class "Default")
      (node (ref "C28") (pin "2") (pinfunction "2_2") (pintype "passive"))
      (node (ref "U9") (pin "27") (pinfunction "CPL_27") (pintype "passive"))
    )
    (net (code "89") (name "Net-(U9-VCP)") (class "Default")
      (node (ref "C29") (pin "2") (pinfunction "2_2") (pintype "passive"))
      (node (ref "U9") (pin "1") (pinfunction "VCP_1") (pintype "passive"))
    )
    (net (code "90") (name "Net-(U9-VREFA)") (class "Default")
      (node (ref "R16") (pin "1") (pinfunction "1_1") (pintype "passive"))
      (node (ref "R20") (pin "2") (pinfunction "2_2") (pintype "passive"))
      (node (ref "U9") (pin "17") (pinfunction "VREFB_17") (pintype "passive"))
      (node (ref "U9") (pin "18") (pinfunction "VREFA_18") (pintype "passive"))
    )
    (net (code "91") (name "Net-(U10-CPH)") (class "Default")
      (node (ref "C36") (pin "1") (pinfunction "1_1") (pintype "passive"))
      (node (ref "U10") (pin "28") (pinfunction "CPH_28") (pintype "passive"))
    )
    (net (code "92") (name "Net-(U10-CPL)") (class "Default")
      (node (ref "C36") (pin "2") (pinfunction "2_2") (pintype "passive"))
      (node (ref "U10") (pin "27") (pinfunction "CPL_27") (pintype "passive"))
    )
    (net (code "93") (name "Net-(U10-VCP)") (class "Default")
      (node (ref "C37") (pin "2") (pinfunction "2_2") (pintype "passive"))
      (node (ref "U10") (pin "1") (pinfunction "VCP_1") (pintype "passive"))
    )
    (net (code "94") (name "Net-(U10-VREFA)") (class "Default")
      (node (ref "R21") (pin "1") (pinfunction "1_1") (pintype "passive"))
      (node (ref "R25") (pin "2") (pinfunction "2_2") (pintype "passive"))
      (node (ref "U10") (pin "17") (pinfunction "VREFB_17") (pintype "passive"))
      (node (ref "U10") (pin "18") (pinfunction "VREFA_18") (pintype "passive"))
    )
    (net (code "95") (name "Net-(U11-CPH)") (class "Default")
      (node (ref "C38") (pin "1") (pinfunction "1_1") (pintype "passive"))
      (node (ref "U11") (pin "28") (pinfunction "CPH_28") (pintype "passive"))
    )
    (net (code "96") (name "Net-(U11-CPL)") (class "Default")
      (node (ref "C38") (pin "2") (pinfunction "2_2") (pintype "passive"))
      (node (ref "U11") (pin "27") (pinfunction "CPL_27") (pintype "passive"))
    )
    (net (code "97") (name "Net-(U11-VCP)") (class "Default")
      (node (ref "C39") (pin "2") (pinfunction "2_2") (pintype "passive"))
      (node (ref "U11") (pin "1") (pinfunction "VCP_1") (pintype "passive"))
    )
    (net (code "98") (name "Net-(U11-VREFA)") (class "Default")
      (node (ref "R22") (pin "1") (pinfunction "1_1") (pintype "passive"))
      (node (ref "R26") (pin "2") (pinfunction "2_2") (pintype "passive"))
      (node (ref "U11") (pin "17") (pinfunction "VREFB_17") (pintype "passive"))
      (node (ref "U11") (pin "18") (pinfunction "VREFA_18") (pintype "passive"))
    )
    (net (code "99") (name "Net-(U12-CPH)") (class "Default")
      (node (ref "C46") (pin "1") (pinfunction "1_1") (pintype "passive"))
      (node (ref "U12") (pin "28") (pinfunction "CPH_28") (pintype "passive"))
    )
    (net (code "100") (name "Net-(U12-CPL)") (class "Default")
      (node (ref "C46") (pin "2") (pinfunction "2_2") (pintype "passive"))
      (node (ref "U12") (pin "27") (pinfunction "CPL_27") (pintype "passive"))
    )
    (net (code "101") (name "Net-(U12-VCP)") (class "Default")
      (node (ref "C47") (pin "2") (pinfunction "2_2") (pintype "passive"))
      (node (ref "U12") (pin "1") (pinfunction "VCP_1") (pintype "passive"))
    )
    (net (code "102") (name "Net-(U12-VREFA)") (class "Default")
      (node (ref "R27") (pin "1") (pinfunction "1_1") (pintype "passive"))
      (node (ref "R31") (pin "2") (pinfunction "2_2") (pintype "passive"))
      (node (ref "U12") (pin "17") (pinfunction "VREFB_17") (pintype "passive"))
      (node (ref "U12") (pin "18") (pinfunction "VREFA_18") (pintype "passive"))
    )
    (net (code "103") (name "Net-(U13-CPH)") (class "Default")
      (node (ref "C48") (pin "1") (pinfunction "1_1") (pintype "passive"))
      (node (ref "U13") (pin "28") (pinfunction "CPH_28") (pintype "passive"))
    )
    (net (code "104") (name "Net-(U13-CPL)") (class "Default")
      (node (ref "C48") (pin "2") (pinfunction "2_2") (pintype "passive"))
      (node (ref "U13") (pin "27") (pinfunction "CPL_27") (pintype "passive"))
    )
    (net (code "105") (name "Net-(U13-VCP)") (class "Default")
      (node (ref "C49") (pin "2") (pinfunction "2_2") (pintype "passive"))
      (node (ref "U13") (pin "1") (pinfunction "VCP_1") (pintype "passive"))
    )
    (net (code "106") (name "Net-(U13-VREFA)") (class "Default")
      (node (ref "R28") (pin "1") (pinfunction "1_1") (pintype "passive"))
      (node (ref "R32") (pin "2") (pinfunction "2_2") (pintype "passive"))
      (node (ref "U13") (pin "17") (pinfunction "VREFB_17") (pintype "passive"))
      (node (ref "U13") (pin "18") (pinfunction "VREFA_18") (pintype "passive"))
    )
    (net (code "107") (name "Net-(U14-CPH)") (class "Default")
      (node (ref "C56") (pin "1") (pinfunction "1_1") (pintype "passive"))
      (node (ref "U14") (pin "28") (pinfunction "CPH_28") (pintype "passive"))
    )
    (net (code "108") (name "Net-(U14-CPL)") (class "Default")
      (node (ref "C56") (pin "2") (pinfunction "2_2") (pintype "passive"))
      (node (ref "U14") (pin "27") (pinfunction "CPL_27") (pintype "passive"))
    )
    (net (code "109") (name "Net-(U14-VCP)") (class "Default")
      (node (ref "C57") (pin "2") (pinfunction "2_2") (pintype "passive"))
      (node (ref "U14") (pin "1") (pinfunction "VCP_1") (pintype "passive"))
    )
    (net (code "110") (name "Net-(U14-VREFA)") (class "Default")
      (node (ref "R33") (pin "1") (pinfunction "1_1") (pintype "passive"))
      (node (ref "R37") (pin "2") (pinfunction "2_2") (pintype "passive"))
      (node (ref "U14") (pin "17") (pinfunction "VREFB_17") (pintype "passive"))
      (node (ref "U14") (pin "18") (pinfunction "VREFA_18") (pintype "passive"))
    )
    (net (code "111") (name "Net-(U15-CPH)") (class "Default")
      (node (ref "C58") (pin "1") (pinfunction "1_1") (pintype "passive"))
      (node (ref "U15") (pin "28") (pinfunction "CPH_28") (pintype "passive"))
    )
    (net (code "112") (name "Net-(U15-CPL)") (class "Default")
      (node (ref "C58") (pin "2") (pinfunction "2_2") (pintype "passive"))
      (node (ref "U15") (pin "27") (pinfunction "CPL_27") (pintype "passive"))
    )
    (net (code "113") (name "Net-(U15-VCP)") (class "Default")
      (node (ref "C59") (pin "2") (pinfunction "2_2") (pintype "passive"))
      (node (ref "U15") (pin "1") (pinfunction "VCP_1") (pintype "passive"))
    )
    (net (code "114") (name "Net-(U15-VREFA)") (class "Default")
      (node (ref "R34") (pin "1") (pinfunction "1_1") (pintype "passive"))
      (node (ref "R38") (pin "2") (pinfunction "2_2") (pintype "passive"))
      (node (ref "U15") (pin "17") (pinfunction "VREFB_17") (pintype "passive"))
      (node (ref "U15") (pin "18") (pinfunction "VREFA_18") (pintype "passive"))
    )
    (net (code "115") (name "VMM") (class "Default")
      (node (ref "C27") (pin "1") (pinfunction "1_1") (pintype "passive"))
      (node (ref "C29") (pin "1") (pinfunction "1_1") (pintype "passive"))
      (node (ref "C30") (pin "1") (pinfunction "1_1") (pintype "passive"))
      (node (ref "C31") (pin "1") (pinfunction "1_1") (pintype "passive"))
      (node (ref "C32") (pin "1") (pinfunction "1_1") (pintype "passive"))
      (node (ref "C33") (pin "1") (pinfunction "1_1") (pintype "passive"))
      (node (ref "C37") (pin "1") (pinfunction "1_1") (pintype "passive"))
      (node (ref "C39") (pin "1") (pinfunction "1_1") (pintype "passive"))
      (node (ref "C40") (pin "1") (pinfunction "1_1") (pintype "passive"))
      (node (ref "C41") (pin "1") (pinfunction "1_1") (pintype "passive"))
      (node (ref "C42") (pin "1") (pinfunction "1_1") (pintype "passive"))
      (node (ref "C43") (pin "1") (pinfunction "1_1") (pintype "passive"))
      (node (ref "C47") (pin "1") (pinfunction "1_1") (pintype "passive"))
      (node (ref "C49") (pin "1") (pinfunction "1_1") (pintype "passive"))
      (node (ref "C50") (pin "1") (pinfunction "1_1") (pintype "passive"))
      (node (ref "C51") (pin "1") (pinfunction "1_1") (pintype "passive"))
      (node (ref "C52") (pin "1") (pinfunction "1_1") (pintype "passive"))
      (node (ref "C53") (pin "1") (pinfunction "1_1") (pintype "passive"))
      (node (ref "C57") (pin "1") (pinfunction "1_1") (pintype "passive"))
      (node (ref "C59") (pin "1") (pinfunction "1_1") (pintype "passive"))
      (node (ref "C60") (pin "1") (pinfunction "1_1") (pintype "passive"))
      (node (ref "C61") (pin "1") (pinfunction "1_1") (pintype "passive"))
      (node (ref "C62") (pin "1") (pinfunction "1_1") (pintype "passive"))
      (node (ref "C63") (pin "1") (pinfunction "1_1") (pintype "passive"))
      (node (ref "ST17") (pin "1") (pinfunction "1_1") (pintype "passive"))
      (node (ref "U10") (pin "13") (pinfunction "VM_13") (pintype "passive"))
      (node (ref "U10") (pin "2") (pinfunction "VM_2") (pintype "passive"))
      (node (ref "U11") (pin "13") (pinfunction "VM_13") (pintype "passive"))
      (node (ref "U11") (pin "2") (pinfunction "VM_2") (pintype "passive"))
      (node (ref "U12") (pin "13") (pinfunction "VM_13") (pintype "passive"))
      (node (ref "U12") (pin "2") (pinfunction "VM_2") (pintype "passive"))
      (node (ref "U13") (pin "13") (pinfunction "VM_13") (pintype "passive"))
      (node (ref "U13") (pin "2") (pinfunction "VM_2") (pintype "passive"))
      (node (ref "U14") (pin "13") (pinfunction "VM_13") (pintype "passive"))
      (node (ref "U14") (pin "2") (pinfunction "VM_2") (pintype "passive"))
      (node (ref "U15") (pin "13") (pinfunction "VM_13") (pintype "passive"))
      (node (ref "U15") (pin "2") (pinfunction "VM_2") (pintype "passive"))
      (node (ref "U8") (pin "13") (pinfunction "VM_13") (pintype "passive"))
      (node (ref "U8") (pin "2") (pinfunction "VM_2") (pintype "passive"))
      (node (ref "U9") (pin "13") (pinfunction "VM_13") (pintype "passive"))
      (node (ref "U9") (pin "2") (pinfunction "VM_2") (pintype "passive"))
    )
  )
)
